# fpga-bank2-outside.net
KiCad netlist of a schematic drawn in Altium Designer
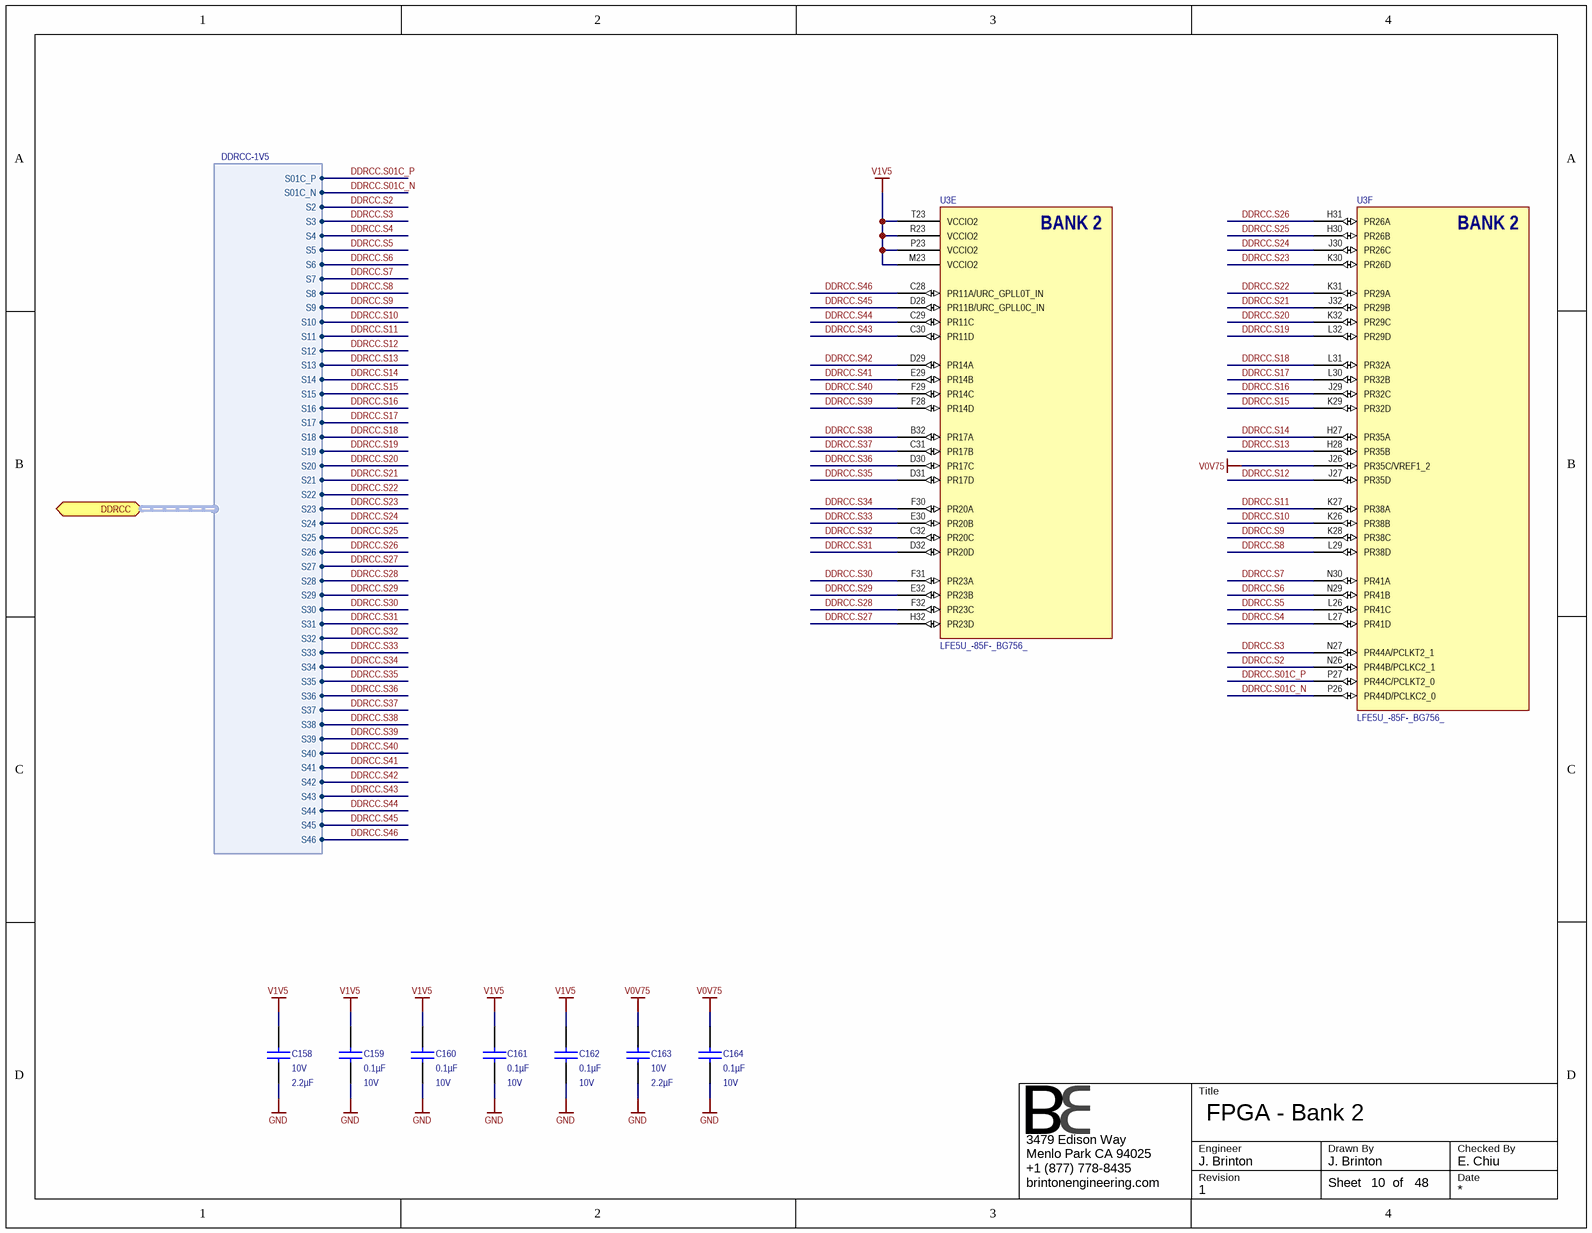
[diagram p0: fpga-bank2-outside.SchDoc]

(export (version "E")
  (design (tool "Eeschema 10.0.6"))
  (components
    (comp (ref "C158")
      (value "GRM188R71A225KE15D")
      (footprint "CAPC1608X90N")
      (description "CAP CER 2.2UF 10V 10% X7R 0603")
      (fields
        (field (name "MANUFACTURER") "Murata Electronics North America")
        (field (name "TOLERANCE") "±10%")
        (field (name "VOLTAGE - RATED") "10V")
        (field (name "CAPACITANCE") "2.2µF")
      )
      (libsource (lib "murata") (part "GRM188R71A225KE15D"))
    )
    (comp (ref "C159")
      (value "GRM155R71A104KA01J")
      (footprint "CAPC1005X56N")
      (description "CAP CER 0.1UF 10V 10% X7R 0402")
      (fields
        (field (name "MANUFACTURER") "Murata Electronics North America")
        (field (name "TOLERANCE") "±10%")
        (field (name "CAPACITANCE") "0.1µF")
        (field (name "VOLTAGE - RATED") "10V")
      )
      (libsource (lib "murata") (part "GRM155R71A104KA01J"))
    )
    (comp (ref "C160")
      (value "GRM155R71A104KA01J")
      (footprint "CAPC1005X56N")
      (description "CAP CER 0.1UF 10V 10% X7R 0402")
      (fields
        (field (name "MANUFACTURER") "Murata Electronics North America")
        (field (name "TOLERANCE") "±10%")
        (field (name "CAPACITANCE") "0.1µF")
        (field (name "VOLTAGE - RATED") "10V")
      )
      (libsource (lib "murata") (part "GRM155R71A104KA01J"))
    )
    (comp (ref "C161")
      (value "GRM155R71A104KA01J")
      (footprint "CAPC1005X56N")
      (description "CAP CER 0.1UF 10V 10% X7R 0402")
      (fields
        (field (name "MANUFACTURER") "Murata Electronics North America")
        (field (name "TOLERANCE") "±10%")
        (field (name "CAPACITANCE") "0.1µF")
        (field (name "VOLTAGE - RATED") "10V")
      )
      (libsource (lib "murata") (part "GRM155R71A104KA01J"))
    )
    (comp (ref "C162")
      (value "GRM155R71A104KA01J")
      (footprint "CAPC1005X56N")
      (description "CAP CER 0.1UF 10V 10% X7R 0402")
      (fields
        (field (name "MANUFACTURER") "Murata Electronics North America")
        (field (name "TOLERANCE") "±10%")
        (field (name "CAPACITANCE") "0.1µF")
        (field (name "VOLTAGE - RATED") "10V")
      )
      (libsource (lib "murata") (part "GRM155R71A104KA01J"))
    )
    (comp (ref "C163")
      (value "GRM188R71A225KE15D")
      (footprint "CAPC1608X90N")
      (description "CAP CER 2.2UF 10V 10% X7R 0603")
      (fields
        (field (name "MANUFACTURER") "Murata Electronics North America")
        (field (name "TOLERANCE") "±10%")
        (field (name "VOLTAGE - RATED") "10V")
        (field (name "CAPACITANCE") "2.2µF")
      )
      (libsource (lib "murata") (part "GRM188R71A225KE15D"))
    )
    (comp (ref "C164")
      (value "GRM155R71A104KA01J")
      (footprint "CAPC1005X56N")
      (description "CAP CER 0.1UF 10V 10% X7R 0402")
      (fields
        (field (name "MANUFACTURER") "Murata Electronics North America")
        (field (name "TOLERANCE") "±10%")
        (field (name "CAPACITANCE") "0.1µF")
        (field (name "VOLTAGE - RATED") "10V")
      )
      (libsource (lib "murata") (part "GRM155R71A104KA01J"))
    )
    (comp (ref "U3")
      (value "LFE5U_-85F-_BG756_")
      (footprint "lattice:caBGA756")
      (description "ECP5 FPGA, 85k LUT, 756-caBGA")
      (fields (field (name "MANUFACTURER") "Lattice Semiconductor"))
      (libsource (lib "lattice") (part "LFE5U_-85F-_BG756_"))
    )
  )
  (nets
    (net (code "2") (name "/DDRCC.S01C_N") (class "Default")
      (node (ref "U3") (pin "P26") (pinfunction "PR44D/PCLKC2_0_P26") (pintype "bidirectional"))
    )
    (net (code "3") (name "/DDRCC.S01C_P") (class "Default")
      (node (ref "U3") (pin "P27") (pinfunction "PR44C/PCLKT2_0_P27") (pintype "bidirectional"))
    )
    (net (code "4") (name "/DDRCC.S2") (class "Default")
      (node (ref "U3") (pin "N26") (pinfunction "PR44B/PCLKC2_1_N26") (pintype "bidirectional"))
    )
    (net (code "5") (name "/DDRCC.S3") (class "Default")
      (node (ref "U3") (pin "N27") (pinfunction "PR44A/PCLKT2_1_N27") (pintype "bidirectional"))
    )
    (net (code "6") (name "/DDRCC.S4") (class "Default")
      (node (ref "U3") (pin "L27") (pinfunction "PR41D_L27") (pintype "bidirectional"))
    )
    (net (code "7") (name "/DDRCC.S5") (class "Default")
      (node (ref "U3") (pin "L26") (pinfunction "PR41C_L26") (pintype "bidirectional"))
    )
    (net (code "8") (name "/DDRCC.S6") (class "Default")
      (node (ref "U3") (pin "N29") (pinfunction "PR41B_N29") (pintype "bidirectional"))
    )
    (net (code "9") (name "/DDRCC.S7") (class "Default")
      (node (ref "U3") (pin "N30") (pinfunction "PR41A_N30") (pintype "bidirectional"))
    )
    (net (code "10") (name "/DDRCC.S8") (class "Default")
      (node (ref "U3") (pin "L29") (pinfunction "PR38D_L29") (pintype "bidirectional"))
    )
    (net (code "11") (name "/DDRCC.S9") (class "Default")
      (node (ref "U3") (pin "K28") (pinfunction "PR38C_K28") (pintype "bidirectional"))
    )
    (net (code "12") (name "/DDRCC.S10") (class "Default")
      (node (ref "U3") (pin "K26") (pinfunction "PR38B_K26") (pintype "bidirectional"))
    )
    (net (code "13") (name "/DDRCC.S11") (class "Default")
      (node (ref "U3") (pin "K27") (pinfunction "PR38A_K27") (pintype "bidirectional"))
    )
    (net (code "14") (name "/DDRCC.S12") (class "Default")
      (node (ref "U3") (pin "J27") (pinfunction "PR35D_J27") (pintype "bidirectional"))
    )
    (net (code "15") (name "/DDRCC.S13") (class "Default")
      (node (ref "U3") (pin "H28") (pinfunction "PR35B_H28") (pintype "bidirectional"))
    )
    (net (code "16") (name "/DDRCC.S14") (class "Default")
      (node (ref "U3") (pin "H27") (pinfunction "PR35A_H27") (pintype "bidirectional"))
    )
    (net (code "17") (name "/DDRCC.S15") (class "Default")
      (node (ref "U3") (pin "K29") (pinfunction "PR32D_K29") (pintype "bidirectional"))
    )
    (net (code "18") (name "/DDRCC.S16") (class "Default")
      (node (ref "U3") (pin "J29") (pinfunction "PR32C_J29") (pintype "bidirectional"))
    )
    (net (code "19") (name "/DDRCC.S17") (class "Default")
      (node (ref "U3") (pin "L30") (pinfunction "PR32B_L30") (pintype "bidirectional"))
    )
    (net (code "20") (name "/DDRCC.S18") (class "Default")
      (node (ref "U3") (pin "L31") (pinfunction "PR32A_L31") (pintype "bidirectional"))
    )
    (net (code "21") (name "/DDRCC.S19") (class "Default")
      (node (ref "U3") (pin "L32") (pinfunction "PR29D_L32") (pintype "bidirectional"))
    )
    (net (code "22") (name "/DDRCC.S20") (class "Default")
      (node (ref "U3") (pin "K32") (pinfunction "PR29C_K32") (pintype "bidirectional"))
    )
    (net (code "23") (name "/DDRCC.S21") (class "Default")
      (node (ref "U3") (pin "J32") (pinfunction "PR29B_J32") (pintype "bidirectional"))
    )
    (net (code "24") (name "/DDRCC.S22") (class "Default")
      (node (ref "U3") (pin "K31") (pinfunction "PR29A_K31") (pintype "bidirectional"))
    )
    (net (code "25") (name "/DDRCC.S23") (class "Default")
      (node (ref "U3") (pin "K30") (pinfunction "PR26D_K30") (pintype "bidirectional"))
    )
    (net (code "26") (name "/DDRCC.S24") (class "Default")
      (node (ref "U3") (pin "J30") (pinfunction "PR26C_J30") (pintype "bidirectional"))
    )
    (net (code "27") (name "/DDRCC.S25") (class "Default")
      (node (ref "U3") (pin "H30") (pinfunction "PR26B_H30") (pintype "bidirectional"))
    )
    (net (code "28") (name "/DDRCC.S26") (class "Default")
      (node (ref "U3") (pin "H31") (pinfunction "PR26A_H31") (pintype "bidirectional"))
    )
    (net (code "29") (name "/DDRCC.S27") (class "Default")
      (node (ref "U3") (pin "H32") (pinfunction "PR23D_H32") (pintype "bidirectional"))
    )
    (net (code "30") (name "/DDRCC.S28") (class "Default")
      (node (ref "U3") (pin "F32") (pinfunction "PR23C_F32") (pintype "bidirectional"))
    )
    (net (code "31") (name "/DDRCC.S29") (class "Default")
      (node (ref "U3") (pin "E32") (pinfunction "PR23B_E32") (pintype "bidirectional"))
    )
    (net (code "32") (name "/DDRCC.S30") (class "Default")
      (node (ref "U3") (pin "F31") (pinfunction "PR23A_F31") (pintype "bidirectional"))
    )
    (net (code "33") (name "/DDRCC.S31") (class "Default")
      (node (ref "U3") (pin "D32") (pinfunction "PR20D_D32") (pintype "bidirectional"))
    )
    (net (code "34") (name "/DDRCC.S32") (class "Default")
      (node (ref "U3") (pin "C32") (pinfunction "PR20C_C32") (pintype "bidirectional"))
    )
    (net (code "35") (name "/DDRCC.S33") (class "Default")
      (node (ref "U3") (pin "E30") (pinfunction "PR20B_E30") (pintype "bidirectional"))
    )
    (net (code "36") (name "/DDRCC.S34") (class "Default")
      (node (ref "U3") (pin "F30") (pinfunction "PR20A_F30") (pintype "bidirectional"))
    )
    (net (code "37") (name "/DDRCC.S35") (class "Default")
      (node (ref "U3") (pin "D31") (pinfunction "PR17D_D31") (pintype "bidirectional"))
    )
    (net (code "38") (name "/DDRCC.S36") (class "Default")
      (node (ref "U3") (pin "D30") (pinfunction "PR17C_D30") (pintype "bidirectional"))
    )
    (net (code "39") (name "/DDRCC.S37") (class "Default")
      (node (ref "U3") (pin "C31") (pinfunction "PR17B_C31") (pintype "bidirectional"))
    )
    (net (code "40") (name "/DDRCC.S38") (class "Default")
      (node (ref "U3") (pin "B32") (pinfunction "PR17A_B32") (pintype "bidirectional"))
    )
    (net (code "41") (name "/DDRCC.S39") (class "Default")
      (node (ref "U3") (pin "F28") (pinfunction "PR14D_F28") (pintype "bidirectional"))
    )
    (net (code "42") (name "/DDRCC.S40") (class "Default")
      (node (ref "U3") (pin "F29") (pinfunction "PR14C_F29") (pintype "bidirectional"))
    )
    (net (code "43") (name "/DDRCC.S41") (class "Default")
      (node (ref "U3") (pin "E29") (pinfunction "PR14B_E29") (pintype "bidirectional"))
    )
    (net (code "44") (name "/DDRCC.S42") (class "Default")
      (node (ref "U3") (pin "D29") (pinfunction "PR14A_D29") (pintype "bidirectional"))
    )
    (net (code "45") (name "/DDRCC.S43") (class "Default")
      (node (ref "U3") (pin "C30") (pinfunction "PR11D_C30") (pintype "bidirectional"))
    )
    (net (code "46") (name "/DDRCC.S44") (class "Default")
      (node (ref "U3") (pin "C29") (pinfunction "PR11C_C29") (pintype "bidirectional"))
    )
    (net (code "47") (name "/DDRCC.S45") (class "Default")
      (node (ref "U3") (pin "D28") (pinfunction "PR11B/URC_GPLL0C_IN_D28") (pintype "bidirectional"))
    )
    (net (code "48") (name "/DDRCC.S46") (class "Default")
      (node (ref "U3") (pin "C28") (pinfunction "PR11A/URC_GPLL0T_IN_C28") (pintype "bidirectional"))
    )
    (net (code "50") (name "GND") (class "Default")
      (node (ref "C158") (pin "1") (pinfunction "1_1") (pintype "passive"))
      (node (ref "C159") (pin "1") (pinfunction "1_1") (pintype "passive"))
      (node (ref "C160") (pin "1") (pinfunction "1_1") (pintype "passive"))
      (node (ref "C161") (pin "1") (pinfunction "1_1") (pintype "passive"))
      (node (ref "C162") (pin "1") (pinfunction "1_1") (pintype "passive"))
      (node (ref "C163") (pin "1") (pinfunction "1_1") (pintype "passive"))
      (node (ref "C164") (pin "1") (pinfunction "1_1") (pintype "passive"))
    )
    (net (code "51") (name "V0V75") (class "Default")
      (node (ref "C163") (pin "2") (pinfunction "2_2") (pintype "passive"))
      (node (ref "C164") (pin "2") (pinfunction "2_2") (pintype "passive"))
      (node (ref "U3") (pin "J26") (pinfunction "PR35C/VREF1_2_J26") (pintype "bidirectional"))
    )
    (net (code "52") (name "V1V5") (class "Default")
      (node (ref "C158") (pin "2") (pinfunction "2_2") (pintype "passive"))
      (node (ref "C159") (pin "2") (pinfunction "2_2") (pintype "passive"))
      (node (ref "C160") (pin "2") (pinfunction "2_2") (pintype "passive"))
      (node (ref "C161") (pin "2") (pinfunction "2_2") (pintype "passive"))
      (node (ref "C162") (pin "2") (pinfunction "2_2") (pintype "passive"))
      (node (ref "U3") (pin "M23") (pinfunction "VCCIO2_M23") (pintype "power_in"))
      (node (ref "U3") (pin "P23") (pinfunction "VCCIO2_P23") (pintype "power_in"))
      (node (ref "U3") (pin "R23") (pinfunction "VCCIO2_R23") (pintype "power_in"))
      (node (ref "U3") (pin "T23") (pinfunction "VCCIO2_T23") (pintype "power_in"))
    )
  )
)
